# christmas_card.net
KiCad netlist of a schematic drawn in EAGLE
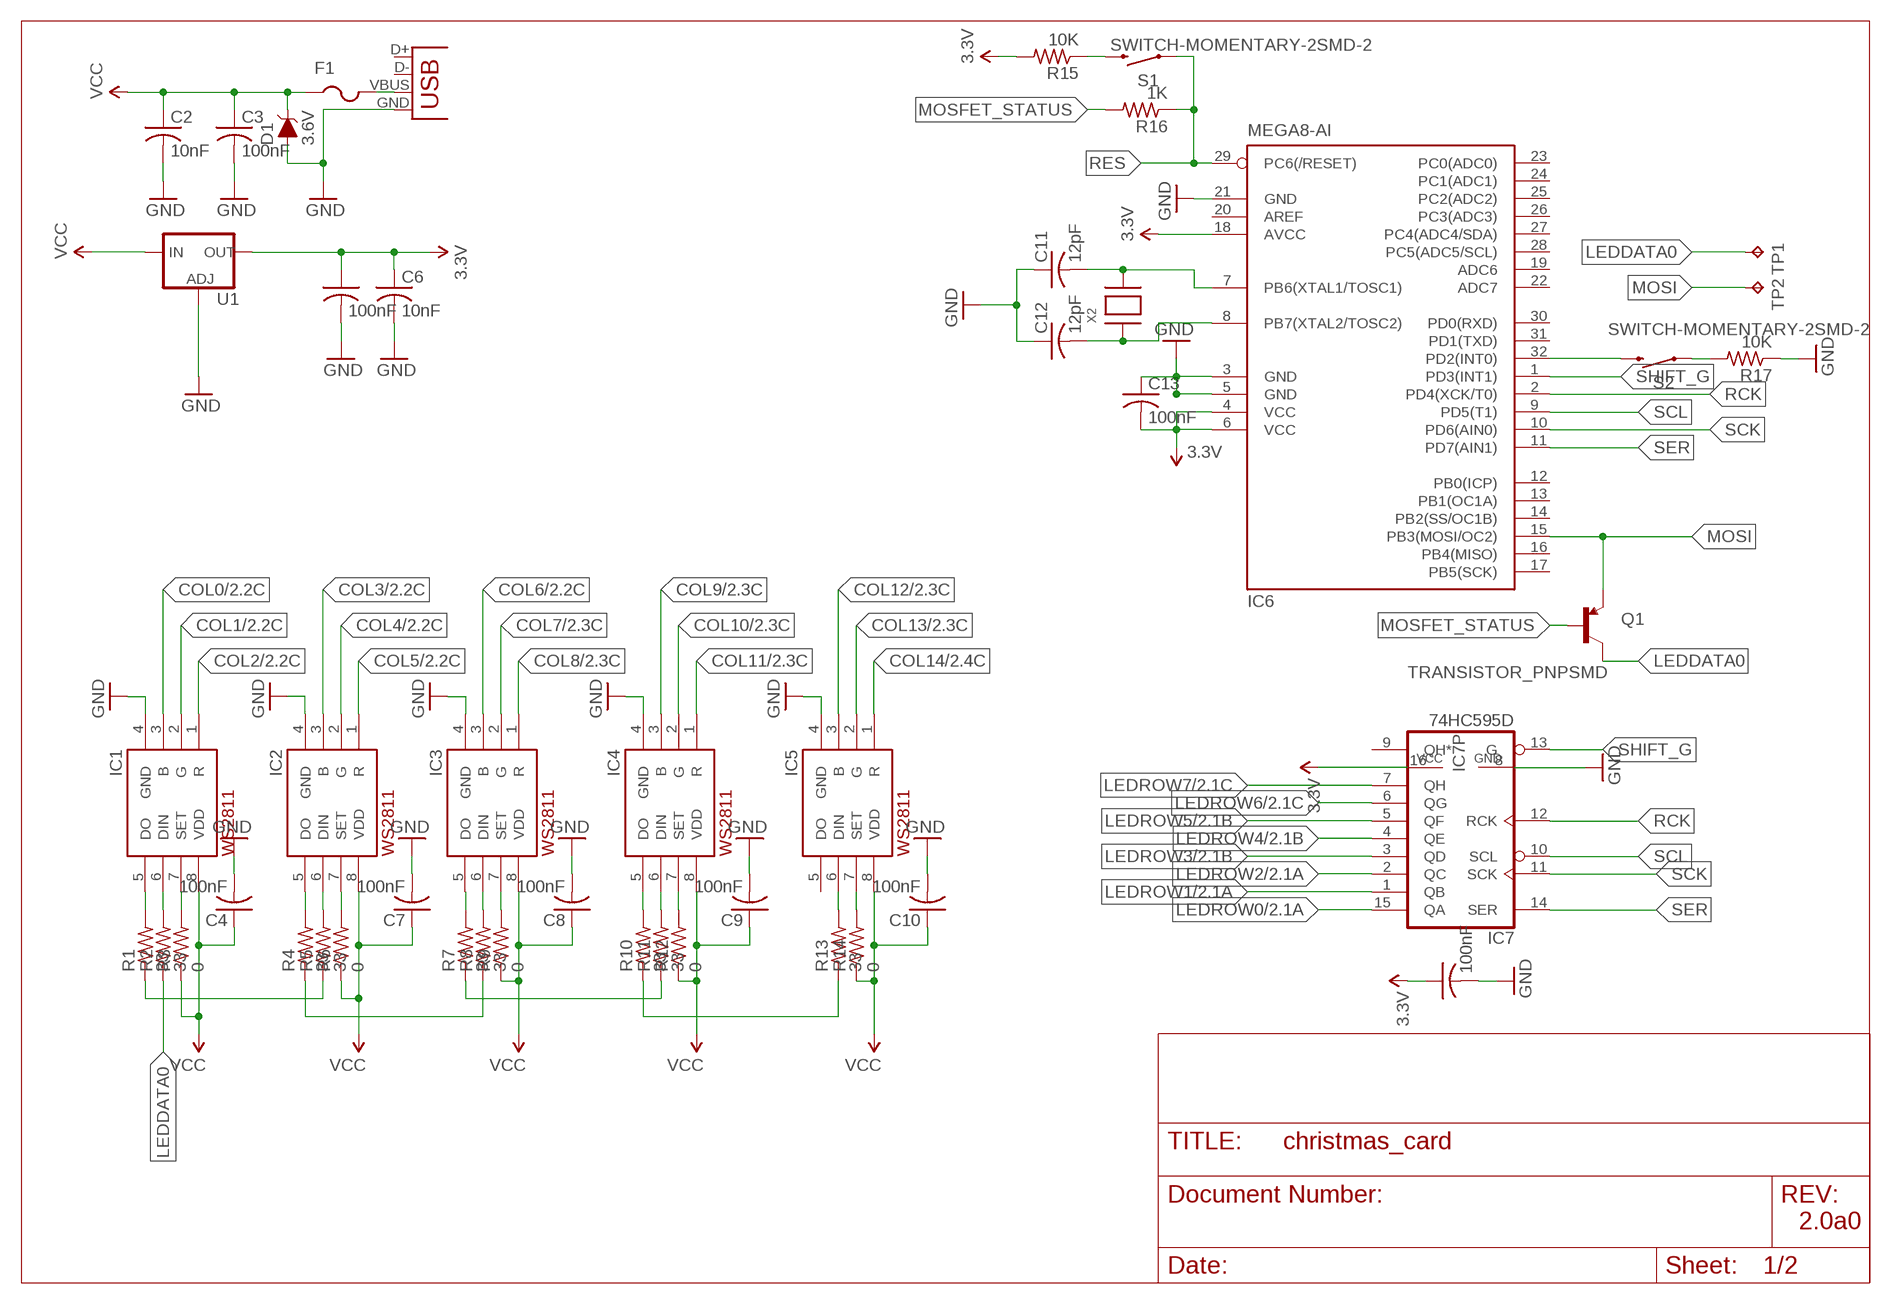
[diagram p0: schematic, sheet 1]
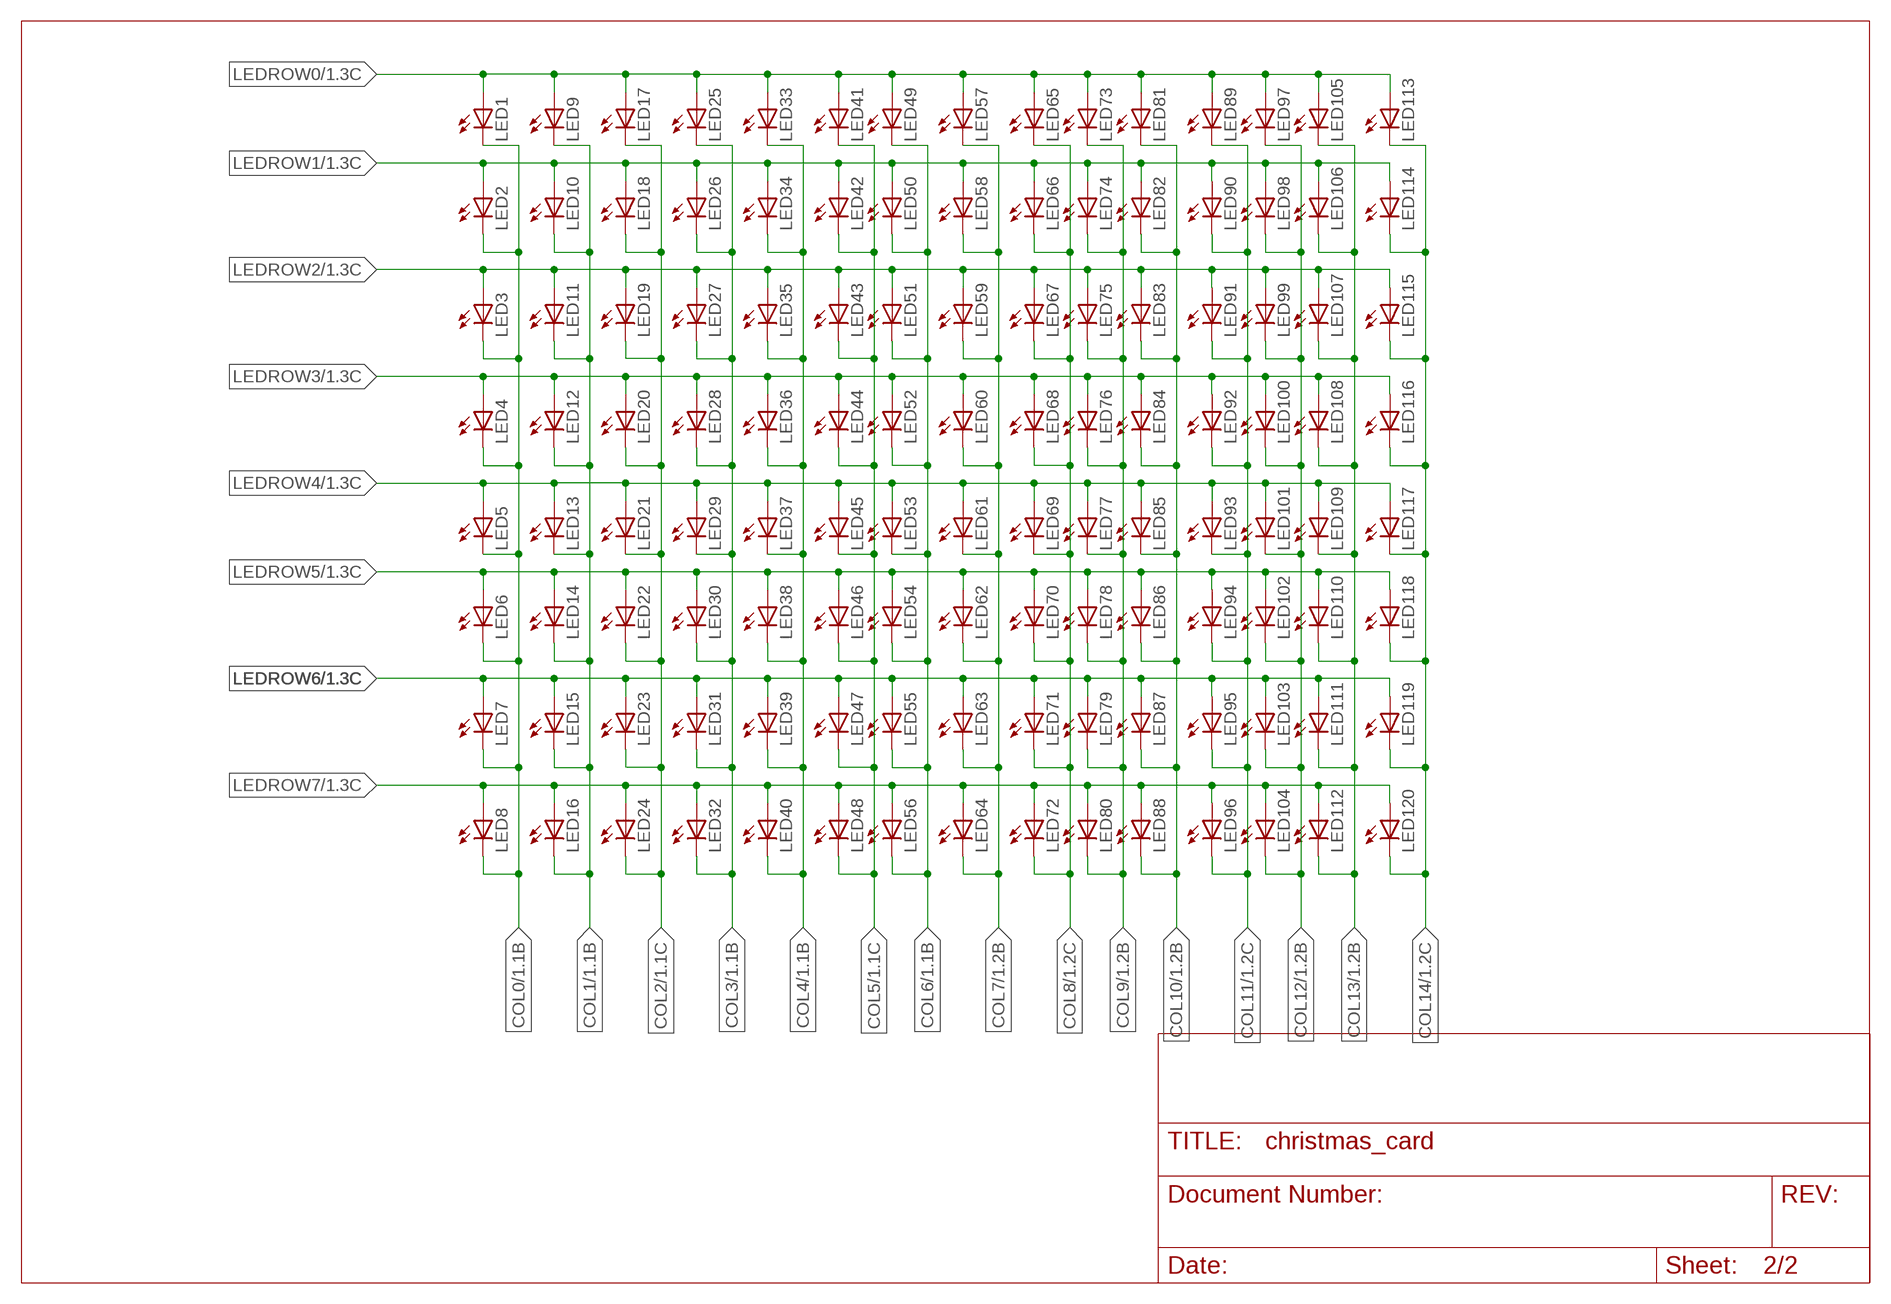
[diagram p1: schematic, sheet 2]

(export (version "E")
  (design (tool "Eeschema 10.0.6"))
  (components
    (comp (ref "LED1")
      (value "LED1206")
      (footprint "eagle-import:LED-1206")
      (libsource (lib "eagle-import") (part "LED1206"))
    )
    (comp (ref "LED2")
      (value "LED1206")
      (footprint "eagle-import:LED-1206")
      (libsource (lib "eagle-import") (part "LED1206"))
    )
    (comp (ref "LED3")
      (value "LED1206")
      (footprint "eagle-import:LED-1206")
      (libsource (lib "eagle-import") (part "LED1206"))
    )
    (comp (ref "LED4")
      (value "LED1206")
      (footprint "eagle-import:LED-1206")
      (libsource (lib "eagle-import") (part "LED1206"))
    )
    (comp (ref "LED5")
      (value "LED1206")
      (footprint "eagle-import:LED-1206")
      (libsource (lib "eagle-import") (part "LED1206"))
    )
    (comp (ref "LED6")
      (value "LED1206")
      (footprint "eagle-import:LED-1206")
      (libsource (lib "eagle-import") (part "LED1206"))
    )
    (comp (ref "LED7")
      (value "LED1206")
      (footprint "eagle-import:LED-1206")
      (libsource (lib "eagle-import") (part "LED1206"))
    )
    (comp (ref "LED8")
      (value "LED1206")
      (footprint "eagle-import:LED-1206")
      (libsource (lib "eagle-import") (part "LED1206"))
    )
    (comp (ref "LED9")
      (value "LED1206")
      (footprint "eagle-import:LED-1206")
      (libsource (lib "eagle-import") (part "LED1206"))
    )
    (comp (ref "LED10")
      (value "LED1206")
      (footprint "eagle-import:LED-1206")
      (libsource (lib "eagle-import") (part "LED1206"))
    )
    (comp (ref "LED11")
      (value "LED1206")
      (footprint "eagle-import:LED-1206")
      (libsource (lib "eagle-import") (part "LED1206"))
    )
    (comp (ref "LED12")
      (value "LED1206")
      (footprint "eagle-import:LED-1206")
      (libsource (lib "eagle-import") (part "LED1206"))
    )
    (comp (ref "LED13")
      (value "LED1206")
      (footprint "eagle-import:LED-1206")
      (libsource (lib "eagle-import") (part "LED1206"))
    )
    (comp (ref "LED14")
      (value "LED1206")
      (footprint "eagle-import:LED-1206")
      (libsource (lib "eagle-import") (part "LED1206"))
    )
    (comp (ref "LED15")
      (value "LED1206")
      (footprint "eagle-import:LED-1206")
      (libsource (lib "eagle-import") (part "LED1206"))
    )
    (comp (ref "LED16")
      (value "LED1206")
      (footprint "eagle-import:LED-1206")
      (libsource (lib "eagle-import") (part "LED1206"))
    )
    (comp (ref "LED17")
      (value "LED1206")
      (footprint "eagle-import:LED-1206")
      (libsource (lib "eagle-import") (part "LED1206"))
    )
    (comp (ref "LED18")
      (value "LED1206")
      (footprint "eagle-import:LED-1206")
      (libsource (lib "eagle-import") (part "LED1206"))
    )
    (comp (ref "LED19")
      (value "LED1206")
      (footprint "eagle-import:LED-1206")
      (libsource (lib "eagle-import") (part "LED1206"))
    )
    (comp (ref "LED20")
      (value "LED1206")
      (footprint "eagle-import:LED-1206")
      (libsource (lib "eagle-import") (part "LED1206"))
    )
    (comp (ref "LED21")
      (value "LED1206")
      (footprint "eagle-import:LED-1206")
      (libsource (lib "eagle-import") (part "LED1206"))
    )
    (comp (ref "LED22")
      (value "LED1206")
      (footprint "eagle-import:LED-1206")
      (libsource (lib "eagle-import") (part "LED1206"))
    )
    (comp (ref "LED23")
      (value "LED1206")
      (footprint "eagle-import:LED-1206")
      (libsource (lib "eagle-import") (part "LED1206"))
    )
    (comp (ref "LED24")
      (value "LED1206")
      (footprint "eagle-import:LED-1206")
      (libsource (lib "eagle-import") (part "LED1206"))
    )
    (comp (ref "LED25")
      (value "LED1206")
      (footprint "eagle-import:LED-1206")
      (libsource (lib "eagle-import") (part "LED1206"))
    )
    (comp (ref "LED26")
      (value "LED1206")
      (footprint "eagle-import:LED-1206")
      (libsource (lib "eagle-import") (part "LED1206"))
    )
    (comp (ref "LED27")
      (value "LED1206")
      (footprint "eagle-import:LED-1206")
      (libsource (lib "eagle-import") (part "LED1206"))
    )
    (comp (ref "LED28")
      (value "LED1206")
      (footprint "eagle-import:LED-1206")
      (libsource (lib "eagle-import") (part "LED1206"))
    )
    (comp (ref "LED29")
      (value "LED1206")
      (footprint "eagle-import:LED-1206")
      (libsource (lib "eagle-import") (part "LED1206"))
    )
    (comp (ref "LED30")
      (value "LED1206")
      (footprint "eagle-import:LED-1206")
      (libsource (lib "eagle-import") (part "LED1206"))
    )
    (comp (ref "LED31")
      (value "LED1206")
      (footprint "eagle-import:LED-1206")
      (libsource (lib "eagle-import") (part "LED1206"))
    )
    (comp (ref "LED32")
      (value "LED1206")
      (footprint "eagle-import:LED-1206")
      (libsource (lib "eagle-import") (part "LED1206"))
    )
    (comp (ref "LED33")
      (value "LED1206")
      (footprint "eagle-import:LED-1206")
      (libsource (lib "eagle-import") (part "LED1206"))
    )
    (comp (ref "LED34")
      (value "LED1206")
      (footprint "eagle-import:LED-1206")
      (libsource (lib "eagle-import") (part "LED1206"))
    )
    (comp (ref "LED35")
      (value "LED1206")
      (footprint "eagle-import:LED-1206")
      (libsource (lib "eagle-import") (part "LED1206"))
    )
    (comp (ref "LED36")
      (value "LED1206")
      (footprint "eagle-import:LED-1206")
      (libsource (lib "eagle-import") (part "LED1206"))
    )
    (comp (ref "LED37")
      (value "LED1206")
      (footprint "eagle-import:LED-1206")
      (libsource (lib "eagle-import") (part "LED1206"))
    )
    (comp (ref "LED38")
      (value "LED1206")
      (footprint "eagle-import:LED-1206")
      (libsource (lib "eagle-import") (part "LED1206"))
    )
    (comp (ref "LED39")
      (value "LED1206")
      (footprint "eagle-import:LED-1206")
      (libsource (lib "eagle-import") (part "LED1206"))
    )
    (comp (ref "LED40")
      (value "LED1206")
      (footprint "eagle-import:LED-1206")
      (libsource (lib "eagle-import") (part "LED1206"))
    )
    (comp (ref "LED41")
      (value "LED1206")
      (footprint "eagle-import:LED-1206")
      (libsource (lib "eagle-import") (part "LED1206"))
    )
    (comp (ref "LED42")
      (value "LED1206")
      (footprint "eagle-import:LED-1206")
      (libsource (lib "eagle-import") (part "LED1206"))
    )
    (comp (ref "LED43")
      (value "LED1206")
      (footprint "eagle-import:LED-1206")
      (libsource (lib "eagle-import") (part "LED1206"))
    )
    (comp (ref "LED44")
      (value "LED1206")
      (footprint "eagle-import:LED-1206")
      (libsource (lib "eagle-import") (part "LED1206"))
    )
    (comp (ref "LED45")
      (value "LED1206")
      (footprint "eagle-import:LED-1206")
      (libsource (lib "eagle-import") (part "LED1206"))
    )
    (comp (ref "LED46")
      (value "LED1206")
      (footprint "eagle-import:LED-1206")
      (libsource (lib "eagle-import") (part "LED1206"))
    )
    (comp (ref "LED47")
      (value "LED1206")
      (footprint "eagle-import:LED-1206")
      (libsource (lib "eagle-import") (part "LED1206"))
    )
    (comp (ref "LED48")
      (value "LED1206")
      (footprint "eagle-import:LED-1206")
      (libsource (lib "eagle-import") (part "LED1206"))
    )
    (comp (ref "LED49")
      (value "LED1206")
      (footprint "eagle-import:LED-1206")
      (libsource (lib "eagle-import") (part "LED1206"))
    )
    (comp (ref "LED50")
      (value "LED1206")
      (footprint "eagle-import:LED-1206")
      (libsource (lib "eagle-import") (part "LED1206"))
    )
    (comp (ref "LED51")
      (value "LED1206")
      (footprint "eagle-import:LED-1206")
      (libsource (lib "eagle-import") (part "LED1206"))
    )
    (comp (ref "LED52")
      (value "LED1206")
      (footprint "eagle-import:LED-1206")
      (libsource (lib "eagle-import") (part "LED1206"))
    )
    (comp (ref "LED53")
      (value "LED1206")
      (footprint "eagle-import:LED-1206")
      (libsource (lib "eagle-import") (part "LED1206"))
    )
    (comp (ref "LED54")
      (value "LED1206")
      (footprint "eagle-import:LED-1206")
      (libsource (lib "eagle-import") (part "LED1206"))
    )
    (comp (ref "LED55")
      (value "LED1206")
      (footprint "eagle-import:LED-1206")
      (libsource (lib "eagle-import") (part "LED1206"))
    )
    (comp (ref "LED56")
      (value "LED1206")
      (footprint "eagle-import:LED-1206")
      (libsource (lib "eagle-import") (part "LED1206"))
    )
    (comp (ref "LED57")
      (value "LED1206")
      (footprint "eagle-import:LED-1206")
      (libsource (lib "eagle-import") (part "LED1206"))
    )
    (comp (ref "LED58")
      (value "LED1206")
      (footprint "eagle-import:LED-1206")
      (libsource (lib "eagle-import") (part "LED1206"))
    )
    (comp (ref "LED59")
      (value "LED1206")
      (footprint "eagle-import:LED-1206")
      (libsource (lib "eagle-import") (part "LED1206"))
    )
    (comp (ref "LED60")
      (value "LED1206")
      (footprint "eagle-import:LED-1206")
      (libsource (lib "eagle-import") (part "LED1206"))
    )
    (comp (ref "LED61")
      (value "LED1206")
      (footprint "eagle-import:LED-1206")
      (libsource (lib "eagle-import") (part "LED1206"))
    )
    (comp (ref "LED62")
      (value "LED1206")
      (footprint "eagle-import:LED-1206")
      (libsource (lib "eagle-import") (part "LED1206"))
    )
    (comp (ref "LED63")
      (value "LED1206")
      (footprint "eagle-import:LED-1206")
      (libsource (lib "eagle-import") (part "LED1206"))
    )
    (comp (ref "LED64")
      (value "LED1206")
      (footprint "eagle-import:LED-1206")
      (libsource (lib "eagle-import") (part "LED1206"))
    )
    (comp (ref "LED65")
      (value "LED1206")
      (footprint "eagle-import:LED-1206")
      (libsource (lib "eagle-import") (part "LED1206"))
    )
    (comp (ref "LED66")
      (value "LED1206")
      (footprint "eagle-import:LED-1206")
      (libsource (lib "eagle-import") (part "LED1206"))
    )
    (comp (ref "LED67")
      (value "LED1206")
      (footprint "eagle-import:LED-1206")
      (libsource (lib "eagle-import") (part "LED1206"))
    )
    (comp (ref "LED68")
      (value "LED1206")
      (footprint "eagle-import:LED-1206")
      (libsource (lib "eagle-import") (part "LED1206"))
    )
    (comp (ref "LED69")
      (value "LED1206")
      (footprint "eagle-import:LED-1206")
      (libsource (lib "eagle-import") (part "LED1206"))
    )
    (comp (ref "LED70")
      (value "LED1206")
      (footprint "eagle-import:LED-1206")
      (libsource (lib "eagle-import") (part "LED1206"))
    )
    (comp (ref "LED71")
      (value "LED1206")
      (footprint "eagle-import:LED-1206")
      (libsource (lib "eagle-import") (part "LED1206"))
    )
    (comp (ref "LED72")
      (value "LED1206")
      (footprint "eagle-import:LED-1206")
      (libsource (lib "eagle-import") (part "LED1206"))
    )
    (comp (ref "LED73")
      (value "LED1206")
      (footprint "eagle-import:LED-1206")
      (libsource (lib "eagle-import") (part "LED1206"))
    )
    (comp (ref "LED74")
      (value "LED1206")
      (footprint "eagle-import:LED-1206")
      (libsource (lib "eagle-import") (part "LED1206"))
    )
    (comp (ref "LED75")
      (value "LED1206")
      (footprint "eagle-import:LED-1206")
      (libsource (lib "eagle-import") (part "LED1206"))
    )
    (comp (ref "LED76")
      (value "LED1206")
      (footprint "eagle-import:LED-1206")
      (libsource (lib "eagle-import") (part "LED1206"))
    )
    (comp (ref "LED77")
      (value "LED1206")
      (footprint "eagle-import:LED-1206")
      (libsource (lib "eagle-import") (part "LED1206"))
    )
    (comp (ref "LED78")
      (value "LED1206")
      (footprint "eagle-import:LED-1206")
      (libsource (lib "eagle-import") (part "LED1206"))
    )
    (comp (ref "LED79")
      (value "LED1206")
      (footprint "eagle-import:LED-1206")
      (libsource (lib "eagle-import") (part "LED1206"))
    )
    (comp (ref "LED80")
      (value "LED1206")
      (footprint "eagle-import:LED-1206")
      (libsource (lib "eagle-import") (part "LED1206"))
    )
    (comp (ref "LED81")
      (value "LED1206")
      (footprint "eagle-import:LED-1206")
      (libsource (lib "eagle-import") (part "LED1206"))
    )
    (comp (ref "LED82")
      (value "LED1206")
      (footprint "eagle-import:LED-1206")
      (libsource (lib "eagle-import") (part "LED1206"))
    )
    (comp (ref "LED83")
      (value "LED1206")
      (footprint "eagle-import:LED-1206")
      (libsource (lib "eagle-import") (part "LED1206"))
    )
    (comp (ref "LED84")
      (value "LED1206")
      (footprint "eagle-import:LED-1206")
      (libsource (lib "eagle-import") (part "LED1206"))
    )
    (comp (ref "LED85")
      (value "LED1206")
      (footprint "eagle-import:LED-1206")
      (libsource (lib "eagle-import") (part "LED1206"))
    )
    (comp (ref "LED86")
      (value "LED1206")
      (footprint "eagle-import:LED-1206")
      (libsource (lib "eagle-import") (part "LED1206"))
    )
    (comp (ref "LED87")
      (value "LED1206")
      (footprint "eagle-import:LED-1206")
      (libsource (lib "eagle-import") (part "LED1206"))
    )
    (comp (ref "LED88")
      (value "LED1206")
      (footprint "eagle-import:LED-1206")
      (libsource (lib "eagle-import") (part "LED1206"))
    )
    (comp (ref "LED89")
      (value "LED1206")
      (footprint "eagle-import:LED-1206")
      (libsource (lib "eagle-import") (part "LED1206"))
    )
    (comp (ref "LED90")
      (value "LED1206")
      (footprint "eagle-import:LED-1206")
      (libsource (lib "eagle-import") (part "LED1206"))
    )
    (comp (ref "LED91")
      (value "LED1206")
      (footprint "eagle-import:LED-1206")
      (libsource (lib "eagle-import") (part "LED1206"))
    )
    (comp (ref "LED92")
      (value "LED1206")
      (footprint "eagle-import:LED-1206")
      (libsource (lib "eagle-import") (part "LED1206"))
    )
    (comp (ref "LED93")
      (value "LED1206")
      (footprint "eagle-import:LED-1206")
      (libsource (lib "eagle-import") (part "LED1206"))
    )
    (comp (ref "LED94")
      (value "LED1206")
      (footprint "eagle-import:LED-1206")
      (libsource (lib "eagle-import") (part "LED1206"))
    )
    (comp (ref "LED95")
      (value "LED1206")
      (footprint "eagle-import:LED-1206")
      (libsource (lib "eagle-import") (part "LED1206"))
    )
    (comp (ref "LED96")
      (value "LED1206")
      (footprint "eagle-import:LED-1206")
      (libsource (lib "eagle-import") (part "LED1206"))
    )
    (comp (ref "LED97")
      (value "LED1206")
      (footprint "eagle-import:LED-1206")
      (libsource (lib "eagle-import") (part "LED1206"))
    )
    (comp (ref "LED98")
      (value "LED1206")
      (footprint "eagle-import:LED-1206")
      (libsource (lib "eagle-import") (part "LED1206"))
    )
    (comp (ref "LED99")
      (value "LED1206")
      (footprint "eagle-import:LED-1206")
      (libsource (lib "eagle-import") (part "LED1206"))
    )
    (comp (ref "LED100")
      (value "LED1206")
      (footprint "eagle-import:LED-1206")
      (libsource (lib "eagle-import") (part "LED1206"))
    )
    (comp (ref "LED101")
      (value "LED1206")
      (footprint "eagle-import:LED-1206")
      (libsource (lib "eagle-import") (part "LED1206"))
    )
    (comp (ref "LED102")
      (value "LED1206")
      (footprint "eagle-import:LED-1206")
      (libsource (lib "eagle-import") (part "LED1206"))
    )
    (comp (ref "LED103")
      (value "LED1206")
      (footprint "eagle-import:LED-1206")
      (libsource (lib "eagle-import") (part "LED1206"))
    )
    (comp (ref "LED104")
      (value "LED1206")
      (footprint "eagle-import:LED-1206")
      (libsource (lib "eagle-import") (part "LED1206"))
    )
    (comp (ref "LED105")
      (value "LED1206")
      (footprint "eagle-import:LED-1206")
      (libsource (lib "eagle-import") (part "LED1206"))
    )
    (comp (ref "LED106")
      (value "LED1206")
      (footprint "eagle-import:LED-1206")
      (libsource (lib "eagle-import") (part "LED1206"))
    )
    (comp (ref "LED107")
      (value "LED1206")
      (footprint "eagle-import:LED-1206")
      (libsource (lib "eagle-import") (part "LED1206"))
    )
    (comp (ref "LED108")
      (value "LED1206")
      (footprint "eagle-import:LED-1206")
      (libsource (lib "eagle-import") (part "LED1206"))
    )
    (comp (ref "LED109")
      (value "LED1206")
      (footprint "eagle-import:LED-1206")
      (libsource (lib "eagle-import") (part "LED1206"))
    )
    (comp (ref "LED110")
      (value "LED1206")
      (footprint "eagle-import:LED-1206")
      (libsource (lib "eagle-import") (part "LED1206"))
    )
    (comp (ref "LED111")
      (value "LED1206")
      (footprint "eagle-import:LED-1206")
      (libsource (lib "eagle-import") (part "LED1206"))
    )
    (comp (ref "LED112")
      (value "LED1206")
      (footprint "eagle-import:LED-1206")
      (libsource (lib "eagle-import") (part "LED1206"))
    )
    (comp (ref "LED113")
      (value "LED1206")
      (footprint "eagle-import:LED-1206")
      (libsource (lib "eagle-import") (part "LED1206"))
    )
    (comp (ref "LED114")
      (value "LED1206")
      (footprint "eagle-import:LED-1206")
      (libsource (lib "eagle-import") (part "LED1206"))
    )
    (comp (ref "LED115")
      (value "LED1206")
      (footprint "eagle-import:LED-1206")
      (libsource (lib "eagle-import") (part "LED1206"))
    )
    (comp (ref "LED116")
      (value "LED1206")
      (footprint "eagle-import:LED-1206")
      (libsource (lib "eagle-import") (part "LED1206"))
    )
    (comp (ref "LED117")
      (value "LED1206")
      (footprint "eagle-import:LED-1206")
      (libsource (lib "eagle-import") (part "LED1206"))
    )
    (comp (ref "LED118")
      (value "LED1206")
      (footprint "eagle-import:LED-1206")
      (libsource (lib "eagle-import") (part "LED1206"))
    )
    (comp (ref "LED119")
      (value "LED1206")
      (footprint "eagle-import:LED-1206")
      (libsource (lib "eagle-import") (part "LED1206"))
    )
    (comp (ref "LED120")
      (value "LED1206")
      (footprint "eagle-import:LED-1206")
      (libsource (lib "eagle-import") (part "LED1206"))
    )
    (comp (ref "C2")
      (value "10nF")
      (footprint "eagle-import:C0603")
      (libsource (lib "eagle-import") (part "C-USC0603"))
    )
    (comp (ref "C3")
      (value "100nF")
      (footprint "eagle-import:C0603")
      (libsource (lib "eagle-import") (part "C-USC0603"))
    )
    (comp (ref "C4")
      (value "100nF")
      (footprint "eagle-import:C0603")
      (libsource (lib "eagle-import") (part "C-USC0603"))
    )
    (comp (ref "C5")
      (value "100nF")
      (footprint "eagle-import:C0603")
      (libsource (lib "eagle-import") (part "C-USC0603"))
    )
    (comp (ref "C6")
      (value "10nF")
      (footprint "eagle-import:C0603")
      (libsource (lib "eagle-import") (part "C-USC0603"))
    )
    (comp (ref "C7")
      (value "100nF")
      (footprint "eagle-import:C0603")
      (libsource (lib "eagle-import") (part "C-USC0603"))
    )
    (comp (ref "C8")
      (value "100nF")
      (footprint "eagle-import:C0603")
      (libsource (lib "eagle-import") (part "C-USC0603"))
    )
    (comp (ref "C9")
      (value "100nF")
      (footprint "eagle-import:C0603")
      (libsource (lib "eagle-import") (part "C-USC0603"))
    )
    (comp (ref "C10")
      (value "100nF")
      (footprint "eagle-import:C0603")
      (libsource (lib "eagle-import") (part "C-USC0603"))
    )
    (comp (ref "C11")
      (value "12pF")
      (footprint "eagle-import:C0603")
      (libsource (lib "eagle-import") (part "C-USC0603"))
    )
    (comp (ref "C12")
      (value "12pF")
      (footprint "eagle-import:C0603")
      (libsource (lib "eagle-import") (part "C-USC0603"))
    )
    (comp (ref "C13")
      (value "100nF")
      (footprint "eagle-import:C0603")
      (libsource (lib "eagle-import") (part "C-USC0603"))
    )
    (comp (ref "C14")
      (value "100nF")
      (footprint "eagle-import:C0603")
      (libsource (lib "eagle-import") (part "C-USC0603"))
    )
    (comp (ref "D1")
      (value "3.6V")
      (footprint "eagle-import:SOD-323")
      (libsource (lib "eagle-import") (part "DIODE-ZENER-BZT52C3V6S"))
    )
    (comp (ref "F1")
      (value "PTCFUSE-1206")
      (footprint "eagle-import:R1206")
      (libsource (lib "eagle-import") (part "PTCFUSE-1206"))
    )
    (comp (ref "IC1")
      (value "WS2811-SOP8")
      (footprint "eagle-import:SO08-SKINNYPADS")
      (libsource (lib "eagle-import") (part "WS2811-SOP8"))
    )
    (comp (ref "IC2")
      (value "WS2811-SOP8")
      (footprint "eagle-import:SO08-SKINNYPADS")
      (libsource (lib "eagle-import") (part "WS2811-SOP8"))
    )
    (comp (ref "IC3")
      (value "WS2811-SOP8")
      (footprint "eagle-import:SO08-SKINNYPADS")
      (libsource (lib "eagle-import") (part "WS2811-SOP8"))
    )
    (comp (ref "IC4")
      (value "WS2811-SOP8")
      (footprint "eagle-import:SO08-SKINNYPADS")
      (libsource (lib "eagle-import") (part "WS2811-SOP8"))
    )
    (comp (ref "IC5")
      (value "WS2811-SOP8")
      (footprint "eagle-import:SO08-SKINNYPADS")
      (libsource (lib "eagle-import") (part "WS2811-SOP8"))
    )
    (comp (ref "IC6")
      (value "MEGA8-AI")
      (footprint "eagle-import:TQFP32-08")
      (fields (field (name "MPN") "ATMEGA8-16AU"))
      (libsource (lib "eagle-import") (part "MEGA8-AI"))
    )
    (comp (ref "IC7")
      (value "74HC595D")
      (footprint "eagle-import:SO16")
      (libsource (lib "eagle-import") (part "74595DHC"))
    )
    (comp (ref "Q1")
      (value "TRANSISTOR_PNPSMD")
      (footprint "eagle-import:SOT23-3")
      (libsource (lib "eagle-import") (part "TRANSISTOR_PNPSMD"))
    )
    (comp (ref "R1")
      (value "33")
      (footprint "eagle-import:R0603")
      (libsource (lib "eagle-import") (part "R-US_R0603"))
    )
    (comp (ref "R2")
      (value "33")
      (footprint "eagle-import:R0603")
      (libsource (lib "eagle-import") (part "R-US_R0603"))
    )
    (comp (ref "R3")
      (value "0")
      (footprint "eagle-import:R0603")
      (libsource (lib "eagle-import") (part "R-US_R0603"))
    )
    (comp (ref "R4")
      (value "33")
      (footprint "eagle-import:R0603")
      (libsource (lib "eagle-import") (part "R-US_R0603"))
    )
    (comp (ref "R5")
      (value "33")
      (footprint "eagle-import:R0603")
      (libsource (lib "eagle-import") (part "R-US_R0603"))
    )
    (comp (ref "R6")
      (value "0")
      (footprint "eagle-import:R0603")
      (libsource (lib "eagle-import") (part "R-US_R0603"))
    )
    (comp (ref "R7")
      (value "33")
      (footprint "eagle-import:R0603")
      (libsource (lib "eagle-import") (part "R-US_R0603"))
    )
    (comp (ref "R8")
      (value "33")
      (footprint "eagle-import:R0603")
      (libsource (lib "eagle-import") (part "R-US_R0603"))
    )
    (comp (ref "R9")
      (value "0")
      (footprint "eagle-import:R0603")
      (libsource (lib "eagle-import") (part "R-US_R0603"))
    )
    (comp (ref "R10")
      (value "33")
      (footprint "eagle-import:R0603")
      (libsource (lib "eagle-import") (part "R-US_R0603"))
    )
    (comp (ref "R11")
      (value "33")
      (footprint "eagle-import:R0603")
      (libsource (lib "eagle-import") (part "R-US_R0603"))
    )
    (comp (ref "R12")
      (value "0")
      (footprint "eagle-import:R0603")
      (libsource (lib "eagle-import") (part "R-US_R0603"))
    )
    (comp (ref "R13")
      (value "33")
      (footprint "eagle-import:R0603")
      (libsource (lib "eagle-import") (part "R-US_R0603"))
    )
    (comp (ref "R14")
      (value "0")
      (footprint "eagle-import:R0603")
      (libsource (lib "eagle-import") (part "R-US_R0603"))
    )
    (comp (ref "R15")
      (value "10K")
      (footprint "eagle-import:R0603")
      (libsource (lib "eagle-import") (part "R-US_R0603"))
    )
    (comp (ref "R16")
      (value "1K")
      (footprint "eagle-import:R0603")
      (libsource (lib "eagle-import") (part "R-US_R0603"))
    )
    (comp (ref "R17")
      (value "10K")
      (footprint "eagle-import:R0603")
      (libsource (lib "eagle-import") (part "R-US_R0603"))
    )
    (comp (ref "S1")
      (value "SWITCH-MOMENTARY-2SMD-2")
      (footprint "eagle-import:TACTILE_SWITCH_SMD-2")
      (libsource (lib "eagle-import") (part "SWITCH-MOMENTARY-2SMD-2"))
    )
    (comp (ref "S2")
      (value "SWITCH-MOMENTARY-2SMD-2")
      (footprint "eagle-import:TACTILE_SWITCH_SMD-2")
      (libsource (lib "eagle-import") (part "SWITCH-MOMENTARY-2SMD-2"))
    )
    (comp (ref "TP1")
      (value "TPB1,27")
      (footprint "eagle-import:B1,27")
      (libsource (lib "eagle-import") (part "TPB1,27"))
    )
    (comp (ref "TP2")
      (value "TPB1,27")
      (footprint "eagle-import:B1,27")
      (libsource (lib "eagle-import") (part "TPB1,27"))
    )
    (comp (ref "U1")
      (value "V_REG_LM1117SOT223")
      (footprint "eagle-import:SOT223")
      (libsource (lib "eagle-import") (part "V_REG_LM1117SOT223"))
    )
    (comp (ref "X1")
      (value "USB-MICROB")
      (footprint "eagle-import:USB-MICROB")
      (libsource (lib "eagle-import") (part "USB-MICROB"))
    )
    (comp (ref "X2")
      (value "XTALNX5032")
      (footprint "eagle-import:NX5032")
      (libsource (lib "eagle-import") (part "XTALNX5032"))
    )
  )
  (nets
    (net (code "1") (name "3.3V") (class "Default")
      (node (ref "C13") (pin "2") (pinfunction "2_2") (pintype "passive"))
      (node (ref "C14") (pin "1") (pinfunction "1_1") (pintype "passive"))
      (node (ref "C5") (pin "1") (pinfunction "1_1") (pintype "passive"))
      (node (ref "C6") (pin "1") (pinfunction "1_1") (pintype "passive"))
      (node (ref "IC6") (pin "18") (pinfunction "AVCC_18") (pintype "power_in"))
      (node (ref "IC6") (pin "4") (pinfunction "VCC_4") (pintype "power_in"))
      (node (ref "IC6") (pin "6") (pinfunction "VCC_6") (pintype "power_in"))
      (node (ref "IC7") (pin "16") (pinfunction "VCC_16") (pintype "power_in"))
      (node (ref "R15") (pin "2") (pinfunction "2_2") (pintype "passive"))
      (node (ref "U1") (pin "2") (pinfunction "OUT_2") (pintype "output"))
      (node (ref "U1") (pin "4") (pinfunction "OUT_4") (pintype "output"))
    )
    (net (code "2") (name "COL0") (class "Default")
      (node (ref "IC1") (pin "3") (pinfunction "B_3") (pintype "open_collector"))
      (node (ref "LED1") (pin "C") (pinfunction "C_C") (pintype "passive"))
      (node (ref "LED2") (pin "C") (pinfunction "C_C") (pintype "passive"))
      (node (ref "LED3") (pin "C") (pinfunction "C_C") (pintype "passive"))
      (node (ref "LED4") (pin "C") (pinfunction "C_C") (pintype "passive"))
      (node (ref "LED5") (pin "C") (pinfunction "C_C") (pintype "passive"))
      (node (ref "LED6") (pin "C") (pinfunction "C_C") (pintype "passive"))
      (node (ref "LED7") (pin "C") (pinfunction "C_C") (pintype "passive"))
      (node (ref "LED8") (pin "C") (pinfunction "C_C") (pintype "passive"))
    )
    (net (code "3") (name "COL1") (class "Default")
      (node (ref "IC1") (pin "2") (pinfunction "G_2") (pintype "open_collector"))
      (node (ref "LED10") (pin "C") (pinfunction "C_C") (pintype "passive"))
      (node (ref "LED11") (pin "C") (pinfunction "C_C") (pintype "passive"))
      (node (ref "LED12") (pin "C") (pinfunction "C_C") (pintype "passive"))
      (node (ref "LED13") (pin "C") (pinfunction "C_C") (pintype "passive"))
      (node (ref "LED14") (pin "C") (pinfunction "C_C") (pintype "passive"))
      (node (ref "LED15") (pin "C") (pinfunction "C_C") (pintype "passive"))
      (node (ref "LED16") (pin "C") (pinfunction "C_C") (pintype "passive"))
      (node (ref "LED9") (pin "C") (pinfunction "C_C") (pintype "passive"))
    )
    (net (code "4") (name "COL2") (class "Default")
      (node (ref "IC1") (pin "1") (pinfunction "R_1") (pintype "open_collector"))
      (node (ref "LED17") (pin "C") (pinfunction "C_C") (pintype "passive"))
      (node (ref "LED18") (pin "C") (pinfunction "C_C") (pintype "passive"))
      (node (ref "LED19") (pin "C") (pinfunction "C_C") (pintype "passive"))
      (node (ref "LED20") (pin "C") (pinfunction "C_C") (pintype "passive"))
      (node (ref "LED21") (pin "C") (pinfunction "C_C") (pintype "passive"))
      (node (ref "LED22") (pin "C") (pinfunction "C_C") (pintype "passive"))
      (node (ref "LED23") (pin "C") (pinfunction "C_C") (pintype "passive"))
      (node (ref "LED24") (pin "C") (pinfunction "C_C") (pintype "passive"))
    )
    (net (code "5") (name "COL3") (class "Default")
      (node (ref "IC2") (pin "3") (pinfunction "B_3") (pintype "open_collector"))
      (node (ref "LED25") (pin "C") (pinfunction "C_C") (pintype "passive"))
      (node (ref "LED26") (pin "C") (pinfunction "C_C") (pintype "passive"))
      (node (ref "LED27") (pin "C") (pinfunction "C_C") (pintype "passive"))
      (node (ref "LED28") (pin "C") (pinfunction "C_C") (pintype "passive"))
      (node (ref "LED29") (pin "C") (pinfunction "C_C") (pintype "passive"))
      (node (ref "LED30") (pin "C") (pinfunction "C_C") (pintype "passive"))
      (node (ref "LED31") (pin "C") (pinfunction "C_C") (pintype "passive"))
      (node (ref "LED32") (pin "C") (pinfunction "C_C") (pintype "passive"))
    )
    (net (code "6") (name "COL4") (class "Default")
      (node (ref "IC2") (pin "2") (pinfunction "G_2") (pintype "open_collector"))
      (node (ref "LED33") (pin "C") (pinfunction "C_C") (pintype "passive"))
      (node (ref "LED34") (pin "C") (pinfunction "C_C") (pintype "passive"))
      (node (ref "LED35") (pin "C") (pinfunction "C_C") (pintype "passive"))
      (node (ref "LED36") (pin "C") (pinfunction "C_C") (pintype "passive"))
      (node (ref "LED37") (pin "C") (pinfunction "C_C") (pintype "passive"))
      (node (ref "LED38") (pin "C") (pinfunction "C_C") (pintype "passive"))
      (node (ref "LED39") (pin "C") (pinfunction "C_C") (pintype "passive"))
      (node (ref "LED40") (pin "C") (pinfunction "C_C") (pintype "passive"))
    )
    (net (code "7") (name "COL5") (class "Default")
      (node (ref "IC2") (pin "1") (pinfunction "R_1") (pintype "open_collector"))
      (node (ref "LED41") (pin "C") (pinfunction "C_C") (pintype "passive"))
      (node (ref "LED42") (pin "C") (pinfunction "C_C") (pintype "passive"))
      (node (ref "LED43") (pin "C") (pinfunction "C_C") (pintype "passive"))
      (node (ref "LED44") (pin "C") (pinfunction "C_C") (pintype "passive"))
      (node (ref "LED45") (pin "C") (pinfunction "C_C") (pintype "passive"))
      (node (ref "LED46") (pin "C") (pinfunction "C_C") (pintype "passive"))
      (node (ref "LED47") (pin "C") (pinfunction "C_C") (pintype "passive"))
      (node (ref "LED48") (pin "C") (pinfunction "C_C") (pintype "passive"))
    )
    (net (code "8") (name "COL6") (class "Default")
      (node (ref "IC3") (pin "3") (pinfunction "B_3") (pintype "open_collector"))
      (node (ref "LED49") (pin "C") (pinfunction "C_C") (pintype "passive"))
      (node (ref "LED50") (pin "C") (pinfunction "C_C") (pintype "passive"))
      (node (ref "LED51") (pin "C") (pinfunction "C_C") (pintype "passive"))
      (node (ref "LED52") (pin "C") (pinfunction "C_C") (pintype "passive"))
      (node (ref "LED53") (pin "C") (pinfunction "C_C") (pintype "passive"))
      (node (ref "LED54") (pin "C") (pinfunction "C_C") (pintype "passive"))
      (node (ref "LED55") (pin "C") (pinfunction "C_C") (pintype "passive"))
      (node (ref "LED56") (pin "C") (pinfunction "C_C") (pintype "passive"))
    )
    (net (code "9") (name "COL7") (class "Default")
      (node (ref "IC3") (pin "2") (pinfunction "G_2") (pintype "open_collector"))
      (node (ref "LED57") (pin "C") (pinfunction "C_C") (pintype "passive"))
      (node (ref "LED58") (pin "C") (pinfunction "C_C") (pintype "passive"))
      (node (ref "LED59") (pin "C") (pinfunction "C_C") (pintype "passive"))
      (node (ref "LED60") (pin "C") (pinfunction "C_C") (pintype "passive"))
      (node (ref "LED61") (pin "C") (pinfunction "C_C") (pintype "passive"))
      (node (ref "LED62") (pin "C") (pinfunction "C_C") (pintype "passive"))
      (node (ref "LED63") (pin "C") (pinfunction "C_C") (pintype "passive"))
      (node (ref "LED64") (pin "C") (pinfunction "C_C") (pintype "passive"))
    )
    (net (code "10") (name "COL8") (class "Default")
      (node (ref "IC3") (pin "1") (pinfunction "R_1") (pintype "open_collector"))
      (node (ref "LED65") (pin "C") (pinfunction "C_C") (pintype "passive"))
      (node (ref "LED66") (pin "C") (pinfunction "C_C") (pintype "passive"))
      (node (ref "LED67") (pin "C") (pinfunction "C_C") (pintype "passive"))
      (node (ref "LED68") (pin "C") (pinfunction "C_C") (pintype "passive"))
      (node (ref "LED69") (pin "C") (pinfunction "C_C") (pintype "passive"))
      (node (ref "LED70") (pin "C") (pinfunction "C_C") (pintype "passive"))
      (node (ref "LED71") (pin "C") (pinfunction "C_C") (pintype "passive"))
      (node (ref "LED72") (pin "C") (pinfunction "C_C") (pintype "passive"))
    )
    (net (code "11") (name "COL9") (class "Default")
      (node (ref "IC4") (pin "3") (pinfunction "B_3") (pintype "open_collector"))
      (node (ref "LED73") (pin "C") (pinfunction "C_C") (pintype "passive"))
      (node (ref "LED74") (pin "C") (pinfunction "C_C") (pintype "passive"))
      (node (ref "LED75") (pin "C") (pinfunction "C_C") (pintype "passive"))
      (node (ref "LED76") (pin "C") (pinfunction "C_C") (pintype "passive"))
      (node (ref "LED77") (pin "C") (pinfunction "C_C") (pintype "passive"))
      (node (ref "LED78") (pin "C") (pinfunction "C_C") (pintype "passive"))
      (node (ref "LED79") (pin "C") (pinfunction "C_C") (pintype "passive"))
      (node (ref "LED80") (pin "C") (pinfunction "C_C") (pintype "passive"))
    )
    (net (code "12") (name "COL10") (class "Default")
      (node (ref "IC4") (pin "2") (pinfunction "G_2") (pintype "open_collector"))
      (node (ref "LED81") (pin "C") (pinfunction "C_C") (pintype "passive"))
      (node (ref "LED82") (pin "C") (pinfunction "C_C") (pintype "passive"))
      (node (ref "LED83") (pin "C") (pinfunction "C_C") (pintype "passive"))
      (node (ref "LED84") (pin "C") (pinfunction "C_C") (pintype "passive"))
      (node (ref "LED85") (pin "C") (pinfunction "C_C") (pintype "passive"))
      (node (ref "LED86") (pin "C") (pinfunction "C_C") (pintype "passive"))
      (node (ref "LED87") (pin "C") (pinfunction "C_C") (pintype "passive"))
      (node (ref "LED88") (pin "C") (pinfunction "C_C") (pintype "passive"))
    )
    (net (code "13") (name "COL11") (class "Default")
      (node (ref "IC4") (pin "1") (pinfunction "R_1") (pintype "open_collector"))
      (node (ref "LED89") (pin "C") (pinfunction "C_C") (pintype "passive"))
      (node (ref "LED90") (pin "C") (pinfunction "C_C") (pintype "passive"))
      (node (ref "LED91") (pin "C") (pinfunction "C_C") (pintype "passive"))
      (node (ref "LED92") (pin "C") (pinfunction "C_C") (pintype "passive"))
      (node (ref "LED93") (pin "C") (pinfunction "C_C") (pintype "passive"))
      (node (ref "LED94") (pin "C") (pinfunction "C_C") (pintype "passive"))
      (node (ref "LED95") (pin "C") (pinfunction "C_C") (pintype "passive"))
      (node (ref "LED96") (pin "C") (pinfunction "C_C") (pintype "passive"))
    )
    (net (code "14") (name "COL12") (class "Default")
      (node (ref "IC5") (pin "3") (pinfunction "B_3") (pintype "open_collector"))
      (node (ref "LED100") (pin "C") (pinfunction "C_C") (pintype "passive"))
      (node (ref "LED101") (pin "C") (pinfunction "C_C") (pintype "passive"))
      (node (ref "LED102") (pin "C") (pinfunction "C_C") (pintype "passive"))
      (node (ref "LED103") (pin "C") (pinfunction "C_C") (pintype "passive"))
      (node (ref "LED104") (pin "C") (pinfunction "C_C") (pintype "passive"))
      (node (ref "LED97") (pin "C") (pinfunction "C_C") (pintype "passive"))
      (node (ref "LED98") (pin "C") (pinfunction "C_C") (pintype "passive"))
      (node (ref "LED99") (pin "C") (pinfunction "C_C") (pintype "passive"))
    )
    (net (code "15") (name "COL13") (class "Default")
      (node (ref "IC5") (pin "2") (pinfunction "G_2") (pintype "open_collector"))
      (node (ref "LED105") (pin "C") (pinfunction "C_C") (pintype "passive"))
      (node (ref "LED106") (pin "C") (pinfunction "C_C") (pintype "passive"))
      (node (ref "LED107") (pin "C") (pinfunction "C_C") (pintype "passive"))
      (node (ref "LED108") (pin "C") (pinfunction "C_C") (pintype "passive"))
      (node (ref "LED109") (pin "C") (pinfunction "C_C") (pintype "passive"))
      (node (ref "LED110") (pin "C") (pinfunction "C_C") (pintype "passive"))
      (node (ref "LED111") (pin "C") (pinfunction "C_C") (pintype "passive"))
      (node (ref "LED112") (pin "C") (pinfunction "C_C") (pintype "passive"))
    )
    (net (code "16") (name "COL14") (class "Default")
      (node (ref "IC5") (pin "1") (pinfunction "R_1") (pintype "open_collector"))
      (node (ref "LED113") (pin "C") (pinfunction "C_C") (pintype "passive"))
      (node (ref "LED114") (pin "C") (pinfunction "C_C") (pintype "passive"))
      (node (ref "LED115") (pin "C") (pinfunction "C_C") (pintype "passive"))
      (node (ref "LED116") (pin "C") (pinfunction "C_C") (pintype "passive"))
      (node (ref "LED117") (pin "C") (pinfunction "C_C") (pintype "passive"))
      (node (ref "LED118") (pin "C") (pinfunction "C_C") (pintype "passive"))
      (node (ref "LED119") (pin "C") (pinfunction "C_C") (pintype "passive"))
      (node (ref "LED120") (pin "C") (pinfunction "C_C") (pintype "passive"))
    )
    (net (code "17") (name "GND") (class "Default")
      (node (ref "C10") (pin "2") (pinfunction "2_2") (pintype "passive"))
      (node (ref "C11") (pin "1") (pinfunction "1_1") (pintype "passive"))
      (node (ref "C12") (pin "1") (pinfunction "1_1") (pintype "passive"))
      (node (ref "C13") (pin "1") (pinfunction "1_1") (pintype "passive"))
      (node (ref "C14") (pin "2") (pinfunction "2_2") (pintype "passive"))
      (node (ref "C2") (pin "2") (pinfunction "2_2") (pintype "passive"))
      (node (ref "C3") (pin "2") (pinfunction "2_2") (pintype "passive"))
      (node (ref "C4") (pin "2") (pinfunction "2_2") (pintype "passive"))
      (node (ref "C5") (pin "2") (pinfunction "2_2") (pintype "passive"))
      (node (ref "C6") (pin "2") (pinfunction "2_2") (pintype "passive"))
      (node (ref "C7") (pin "2") (pinfunction "2_2") (pintype "passive"))
      (node (ref "C8") (pin "2") (pinfunction "2_2") (pintype "passive"))
      (node (ref "C9") (pin "2") (pinfunction "2_2") (pintype "passive"))
      (node (ref "D1") (pin "A") (pinfunction "A_A") (pintype "passive"))
      (node (ref "IC1") (pin "4") (pinfunction "GND_4") (pintype "power_in"))
      (node (ref "IC2") (pin "4") (pinfunction "GND_4") (pintype "power_in"))
      (node (ref "IC3") (pin "4") (pinfunction "GND_4") (pintype "power_in"))
      (node (ref "IC4") (pin "4") (pinfunction "GND_4") (pintype "power_in"))
      (node (ref "IC5") (pin "4") (pinfunction "GND_4") (pintype "power_in"))
      (node (ref "IC6") (pin "21") (pinfunction "GND_21") (pintype "power_in"))
      (node (ref "IC6") (pin "3") (pinfunction "GND_3") (pintype "power_in"))
      (node (ref "IC6") (pin "5") (pinfunction "GND_5") (pintype "power_in"))
      (node (ref "IC7") (pin "8") (pinfunction "GND_8") (pintype "power_in"))
      (node (ref "R17") (pin "1") (pinfunction "1_1") (pintype "passive"))
      (node (ref "U1") (pin "1") (pinfunction "ADJ_1") (pintype "input"))
      (node (ref "X1") (pin "GND") (pinfunction "GND_GND") (pintype "bidirectional"))
    )
    (net (code "18") (name "LEDDATA0") (class "Default")
      (node (ref "Q1") (pin "3") (pinfunction "C_3") (pintype "passive"))
      (node (ref "R2") (pin "1") (pinfunction "1_1") (pintype "passive"))
      (node (ref "TP1") (pin "TP") (pinfunction "TP_TP") (pintype "input"))
    )
    (net (code "19") (name "LEDROW0") (class "Default")
      (node (ref "IC7") (pin "15") (pinfunction "QA_15") (pintype "tri_state"))
      (node (ref "LED1") (pin "A") (pinfunction "A_A") (pintype "passive"))
      (node (ref "LED105") (pin "A") (pinfunction "A_A") (pintype "passive"))
      (node (ref "LED113") (pin "A") (pinfunction "A_A") (pintype "passive"))
      (node (ref "LED17") (pin "A") (pinfunction "A_A") (pintype "passive"))
      (node (ref "LED25") (pin "A") (pinfunction "A_A") (pintype "passive"))
      (node (ref "LED33") (pin "A") (pinfunction "A_A") (pintype "passive"))
      (node (ref "LED41") (pin "A") (pinfunction "A_A") (pintype "passive"))
      (node (ref "LED49") (pin "A") (pinfunction "A_A") (pintype "passive"))
      (node (ref "LED57") (pin "A") (pinfunction "A_A") (pintype "passive"))
      (node (ref "LED65") (pin "A") (pinfunction "A_A") (pintype "passive"))
      (node (ref "LED73") (pin "A") (pinfunction "A_A") (pintype "passive"))
      (node (ref "LED81") (pin "A") (pinfunction "A_A") (pintype "passive"))
      (node (ref "LED89") (pin "A") (pinfunction "A_A") (pintype "passive"))
      (node (ref "LED9") (pin "A") (pinfunction "A_A") (pintype "passive"))
      (node (ref "LED97") (pin "A") (pinfunction "A_A") (pintype "passive"))
    )
    (net (code "20") (name "LEDROW1") (class "Default")
      (node (ref "IC7") (pin "1") (pinfunction "QB_1") (pintype "tri_state"))
      (node (ref "LED10") (pin "A") (pinfunction "A_A") (pintype "passive"))
      (node (ref "LED106") (pin "A") (pinfunction "A_A") (pintype "passive"))
      (node (ref "LED114") (pin "A") (pinfunction "A_A") (pintype "passive"))
      (node (ref "LED18") (pin "A") (pinfunction "A_A") (pintype "passive"))
      (node (ref "LED2") (pin "A") (pinfunction "A_A") (pintype "passive"))
      (node (ref "LED26") (pin "A") (pinfunction "A_A") (pintype "passive"))
      (node (ref "LED34") (pin "A") (pinfunction "A_A") (pintype "passive"))
      (node (ref "LED42") (pin "A") (pinfunction "A_A") (pintype "passive"))
      (node (ref "LED50") (pin "A") (pinfunction "A_A") (pintype "passive"))
      (node (ref "LED58") (pin "A") (pinfunction "A_A") (pintype "passive"))
      (node (ref "LED66") (pin "A") (pinfunction "A_A") (pintype "passive"))
      (node (ref "LED74") (pin "A") (pinfunction "A_A") (pintype "passive"))
      (node (ref "LED82") (pin "A") (pinfunction "A_A") (pintype "passive"))
      (node (ref "LED90") (pin "A") (pinfunction "A_A") (pintype "passive"))
      (node (ref "LED98") (pin "A") (pinfunction "A_A") (pintype "passive"))
    )
    (net (code "21") (name "LEDROW2") (class "Default")
      (node (ref "IC7") (pin "2") (pinfunction "QC_2") (pintype "tri_state"))
      (node (ref "LED107") (pin "A") (pinfunction "A_A") (pintype "passive"))
      (node (ref "LED11") (pin "A") (pinfunction "A_A") (pintype "passive"))
      (node (ref "LED115") (pin "A") (pinfunction "A_A") (pintype "passive"))
      (node (ref "LED19") (pin "A") (pinfunction "A_A") (pintype "passive"))
      (node (ref "LED27") (pin "A") (pinfunction "A_A") (pintype "passive"))
      (node (ref "LED3") (pin "A") (pinfunction "A_A") (pintype "passive"))
      (node (ref "LED35") (pin "A") (pinfunction "A_A") (pintype "passive"))
      (node (ref "LED43") (pin "A") (pinfunction "A_A") (pintype "passive"))
      (node (ref "LED51") (pin "A") (pinfunction "A_A") (pintype "passive"))
      (node (ref "LED59") (pin "A") (pinfunction "A_A") (pintype "passive"))
      (node (ref "LED67") (pin "A") (pinfunction "A_A") (pintype "passive"))
      (node (ref "LED75") (pin "A") (pinfunction "A_A") (pintype "passive"))
      (node (ref "LED83") (pin "A") (pinfunction "A_A") (pintype "passive"))
      (node (ref "LED91") (pin "A") (pinfunction "A_A") (pintype "passive"))
      (node (ref "LED99") (pin "A") (pinfunction "A_A") (pintype "passive"))
    )
    (net (code "22") (name "LEDROW3") (class "Default")
      (node (ref "IC7") (pin "3") (pinfunction "QD_3") (pintype "tri_state"))
      (node (ref "LED100") (pin "A") (pinfunction "A_A") (pintype "passive"))
      (node (ref "LED108") (pin "A") (pinfunction "A_A") (pintype "passive"))
      (node (ref "LED116") (pin "A") (pinfunction "A_A") (pintype "passive"))
      (node (ref "LED12") (pin "A") (pinfunction "A_A") (pintype "passive"))
      (node (ref "LED20") (pin "A") (pinfunction "A_A") (pintype "passive"))
      (node (ref "LED28") (pin "A") (pinfunction "A_A") (pintype "passive"))
      (node (ref "LED36") (pin "A") (pinfunction "A_A") (pintype "passive"))
      (node (ref "LED4") (pin "A") (pinfunction "A_A") (pintype "passive"))
      (node (ref "LED44") (pin "A") (pinfunction "A_A") (pintype "passive"))
      (node (ref "LED52") (pin "A") (pinfunction "A_A") (pintype "passive"))
      (node (ref "LED60") (pin "A") (pinfunction "A_A") (pintype "passive"))
      (node (ref "LED68") (pin "A") (pinfunction "A_A") (pintype "passive"))
      (node (ref "LED76") (pin "A") (pinfunction "A_A") (pintype "passive"))
      (node (ref "LED84") (pin "A") (pinfunction "A_A") (pintype "passive"))
      (node (ref "LED92") (pin "A") (pinfunction "A_A") (pintype "passive"))
    )
    (net (code "23") (name "LEDROW4") (class "Default")
      (node (ref "IC7") (pin "4") (pinfunction "QE_4") (pintype "tri_state"))
      (node (ref "LED101") (pin "A") (pinfunction "A_A") (pintype "passive"))
      (node (ref "LED109") (pin "A") (pinfunction "A_A") (pintype "passive"))
      (node (ref "LED117") (pin "A") (pinfunction "A_A") (pintype "passive"))
      (node (ref "LED13") (pin "A") (pinfunction "A_A") (pintype "passive"))
      (node (ref "LED21") (pin "A") (pinfunction "A_A") (pintype "passive"))
      (node (ref "LED29") (pin "A") (pinfunction "A_A") (pintype "passive"))
      (node (ref "LED37") (pin "A") (pinfunction "A_A") (pintype "passive"))
      (node (ref "LED45") (pin "A") (pinfunction "A_A") (pintype "passive"))
      (node (ref "LED5") (pin "A") (pinfunction "A_A") (pintype "passive"))
      (node (ref "LED53") (pin "A") (pinfunction "A_A") (pintype "passive"))
      (node (ref "LED61") (pin "A") (pinfunction "A_A") (pintype "passive"))
      (node (ref "LED69") (pin "A") (pinfunction "A_A") (pintype "passive"))
      (node (ref "LED77") (pin "A") (pinfunction "A_A") (pintype "passive"))
      (node (ref "LED85") (pin "A") (pinfunction "A_A") (pintype "passive"))
      (node (ref "LED93") (pin "A") (pinfunction "A_A") (pintype "passive"))
    )
    (net (code "24") (name "LEDROW5") (class "Default")
      (node (ref "IC7") (pin "5") (pinfunction "QF_5") (pintype "tri_state"))
      (node (ref "LED102") (pin "A") (pinfunction "A_A") (pintype "passive"))
      (node (ref "LED110") (pin "A") (pinfunction "A_A") (pintype "passive"))
      (node (ref "LED118") (pin "A") (pinfunction "A_A") (pintype "passive"))
      (node (ref "LED14") (pin "A") (pinfunction "A_A") (pintype "passive"))
      (node (ref "LED22") (pin "A") (pinfunction "A_A") (pintype "passive"))
      (node (ref "LED30") (pin "A") (pinfunction "A_A") (pintype "passive"))
      (node (ref "LED38") (pin "A") (pinfunction "A_A") (pintype "passive"))
      (node (ref "LED46") (pin "A") (pinfunction "A_A") (pintype "passive"))
      (node (ref "LED54") (pin "A") (pinfunction "A_A") (pintype "passive"))
      (node (ref "LED6") (pin "A") (pinfunction "A_A") (pintype "passive"))
      (node (ref "LED62") (pin "A") (pinfunction "A_A") (pintype "passive"))
      (node (ref "LED70") (pin "A") (pinfunction "A_A") (pintype "passive"))
      (node (ref "LED78") (pin "A") (pinfunction "A_A") (pintype "passive"))
      (node (ref "LED86") (pin "A") (pinfunction "A_A") (pintype "passive"))
      (node (ref "LED94") (pin "A") (pinfunction "A_A") (pintype "passive"))
    )
    (net (code "25") (name "LEDROW6") (class "Default")
      (node (ref "IC7") (pin "6") (pinfunction "QG_6") (pintype "tri_state"))
      (node (ref "LED103") (pin "A") (pinfunction "A_A") (pintype "passive"))
      (node (ref "LED111") (pin "A") (pinfunction "A_A") (pintype "passive"))
      (node (ref "LED119") (pin "A") (pinfunction "A_A") (pintype "passive"))
      (node (ref "LED15") (pin "A") (pinfunction "A_A") (pintype "passive"))
      (node (ref "LED23") (pin "A") (pinfunction "A_A") (pintype "passive"))
      (node (ref "LED31") (pin "A") (pinfunction "A_A") (pintype "passive"))
      (node (ref "LED39") (pin "A") (pinfunction "A_A") (pintype "passive"))
      (node (ref "LED47") (pin "A") (pinfunction "A_A") (pintype "passive"))
      (node (ref "LED55") (pin "A") (pinfunction "A_A") (pintype "passive"))
      (node (ref "LED63") (pin "A") (pinfunction "A_A") (pintype "passive"))
      (node (ref "LED7") (pin "A") (pinfunction "A_A") (pintype "passive"))
      (node (ref "LED71") (pin "A") (pinfunction "A_A") (pintype "passive"))
      (node (ref "LED79") (pin "A") (pinfunction "A_A") (pintype "passive"))
      (node (ref "LED87") (pin "A") (pinfunction "A_A") (pintype "passive"))
      (node (ref "LED95") (pin "A") (pinfunction "A_A") (pintype "passive"))
    )
    (net (code "26") (name "LEDROW7") (class "Default")
      (node (ref "IC7") (pin "7") (pinfunction "QH_7") (pintype "tri_state"))
      (node (ref "LED104") (pin "A") (pinfunction "A_A") (pintype "passive"))
      (node (ref "LED112") (pin "A") (pinfunction "A_A") (pintype "passive"))
      (node (ref "LED120") (pin "A") (pinfunction "A_A") (pintype "passive"))
      (node (ref "LED16") (pin "A") (pinfunction "A_A") (pintype "passive"))
      (node (ref "LED24") (pin "A") (pinfunction "A_A") (pintype "passive"))
      (node (ref "LED32") (pin "A") (pinfunction "A_A") (pintype "passive"))
      (node (ref "LED40") (pin "A") (pinfunction "A_A") (pintype "passive"))
      (node (ref "LED48") (pin "A") (pinfunction "A_A") (pintype "passive"))
      (node (ref "LED56") (pin "A") (pinfunction "A_A") (pintype "passive"))
      (node (ref "LED64") (pin "A") (pinfunction "A_A") (pintype "passive"))
      (node (ref "LED72") (pin "A") (pinfunction "A_A") (pintype "passive"))
      (node (ref "LED8") (pin "A") (pinfunction "A_A") (pintype "passive"))
      (node (ref "LED80") (pin "A") (pinfunction "A_A") (pintype "passive"))
      (node (ref "LED88") (pin "A") (pinfunction "A_A") (pintype "passive"))
      (node (ref "LED96") (pin "A") (pinfunction "A_A") (pintype "passive"))
    )
    (net (code "27") (name "MOSFET_STATUS") (class "Default")
      (node (ref "Q1") (pin "1") (pinfunction "B_1") (pintype "passive"))
      (node (ref "R16") (pin "2") (pinfunction "2_2") (pintype "passive"))
    )
    (net (code "28") (name "MOSI") (class "Default")
      (node (ref "IC6") (pin "15") (pinfunction "PB3(MOSI/OC2)_15") (pintype "bidirectional"))
      (node (ref "Q1") (pin "2") (pinfunction "E_2") (pintype "passive"))
      (node (ref "TP2") (pin "TP") (pinfunction "TP_TP") (pintype "input"))
    )
    (net (code "29") (name "Net-(F1-Pad2)") (class "Default")
      (node (ref "F1") (pin "2") (pinfunction "2_2") (pintype "passive"))
      (node (ref "X1") (pin "VBUS") (pinfunction "VBUS_VBUS") (pintype "bidirectional"))
    )
    (net (code "30") (name "Net-(IC1-DIN)") (class "Default")
      (node (ref "IC1") (pin "6") (pinfunction "DIN_6") (pintype "input"))
      (node (ref "R2") (pin "2") (pinfunction "2_2") (pintype "passive"))
    )
    (net (code "31") (name "Net-(IC1-DO)") (class "Default")
      (node (ref "IC1") (pin "5") (pinfunction "DO_5") (pintype "output"))
      (node (ref "R1") (pin "2") (pinfunction "2_2") (pintype "passive"))
    )
    (net (code "32") (name "Net-(IC1-SET)") (class "Default")
      (node (ref "IC1") (pin "7") (pinfunction "SET_7") (pintype "input"))
      (node (ref "R3") (pin "2") (pinfunction "2_2") (pintype "passive"))
    )
    (net (code "33") (name "Net-(IC2-DIN)") (class "Default")
      (node (ref "IC2") (pin "6") (pinfunction "DIN_6") (pintype "input"))
      (node (ref "R5") (pin "2") (pinfunction "2_2") (pintype "passive"))
    )
    (net (code "34") (name "Net-(IC2-DO)") (class "Default")
      (node (ref "IC2") (pin "5") (pinfunction "DO_5") (pintype "output"))
      (node (ref "R4") (pin "2") (pinfunction "2_2") (pintype "passive"))
    )
    (net (code "35") (name "Net-(IC2-SET)") (class "Default")
      (node (ref "IC2") (pin "7") (pinfunction "SET_7") (pintype "input"))
      (node (ref "R6") (pin "2") (pinfunction "2_2") (pintype "passive"))
    )
    (net (code "36") (name "Net-(IC3-DIN)") (class "Default")
      (node (ref "IC3") (pin "6") (pinfunction "DIN_6") (pintype "input"))
      (node (ref "R8") (pin "2") (pinfunction "2_2") (pintype "passive"))
    )
    (net (code "37") (name "Net-(IC3-DO)") (class "Default")
      (node (ref "IC3") (pin "5") (pinfunction "DO_5") (pintype "output"))
      (node (ref "R7") (pin "2") (pinfunction "2_2") (pintype "passive"))
    )
    (net (code "38") (name "Net-(IC3-SET)") (class "Default")
      (node (ref "IC3") (pin "7") (pinfunction "SET_7") (pintype "input"))
      (node (ref "R9") (pin "2") (pinfunction "2_2") (pintype "passive"))
    )
    (net (code "39") (name "Net-(IC4-DIN)") (class "Default")
      (node (ref "IC4") (pin "6") (pinfunction "DIN_6") (pintype "input"))
      (node (ref "R11") (pin "2") (pinfunction "2_2") (pintype "passive"))
    )
    (net (code "40") (name "Net-(IC4-DO)") (class "Default")
      (node (ref "IC4") (pin "5") (pinfunction "DO_5") (pintype "output"))
      (node (ref "R10") (pin "2") (pinfunction "2_2") (pintype "passive"))
    )
    (net (code "41") (name "Net-(IC4-SET)") (class "Default")
      (node (ref "IC4") (pin "7") (pinfunction "SET_7") (pintype "input"))
      (node (ref "R12") (pin "2") (pinfunction "2_2") (pintype "passive"))
    )
    (net (code "42") (name "Net-(IC5-DIN)") (class "Default")
      (node (ref "IC5") (pin "6") (pinfunction "DIN_6") (pintype "input"))
      (node (ref "R13") (pin "2") (pinfunction "2_2") (pintype "passive"))
    )
    (net (code "43") (name "Net-(IC5-SET)") (class "Default")
      (node (ref "IC5") (pin "7") (pinfunction "SET_7") (pintype "input"))
      (node (ref "R14") (pin "2") (pinfunction "2_2") (pintype "passive"))
    )
    (net (code "44") (name "Net-(IC6-PB6(XTAL1{slash}TOSC1))") (class "Default")
      (node (ref "C11") (pin "2") (pinfunction "2_2") (pintype "passive"))
      (node (ref "IC6") (pin "7") (pinfunction "PB6(XTAL1/TOSC1)_7") (pintype "bidirectional"))
      (node (ref "X2") (pin "P$2") (pinfunction "P$2_P$2") (pintype "bidirectional"))
    )
    (net (code "45") (name "Net-(IC6-PB7(XTAL2{slash}TOSC2))") (class "Default")
      (node (ref "C12") (pin "2") (pinfunction "2_2") (pintype "passive"))
      (node (ref "IC6") (pin "8") (pinfunction "PB7(XTAL2/TOSC2)_8") (pintype "bidirectional"))
      (node (ref "X2") (pin "P$1") (pinfunction "P$1_P$1") (pintype "bidirectional"))
    )
    (net (code "46") (name "Net-(IC6-PD2(INT0))") (class "Default")
      (node (ref "IC6") (pin "32") (pinfunction "PD2(INT0)_32") (pintype "bidirectional"))
      (node (ref "S2") (pin "1") (pinfunction "2_1") (pintype "passive"))
    )
    (net (code "47") (name "Net-(R1-Pad1)") (class "Default")
      (node (ref "R1") (pin "1") (pinfunction "1_1") (pintype "passive"))
      (node (ref "R5") (pin "1") (pinfunction "1_1") (pintype "passive"))
    )
    (net (code "48") (name "Net-(R4-Pad1)") (class "Default")
      (node (ref "R4") (pin "1") (pinfunction "1_1") (pintype "passive"))
      (node (ref "R8") (pin "1") (pinfunction "1_1") (pintype "passive"))
    )
    (net (code "49") (name "Net-(R10-Pad1)") (class "Default")
      (node (ref "R10") (pin "1") (pinfunction "1_1") (pintype "passive"))
      (node (ref "R13") (pin "1") (pinfunction "1_1") (pintype "passive"))
    )
    (net (code "50") (name "Net-(R11-Pad1)") (class "Default")
      (node (ref "R11") (pin "1") (pinfunction "1_1") (pintype "passive"))
      (node (ref "R7") (pin "1") (pinfunction "1_1") (pintype "passive"))
    )
    (net (code "51") (name "Net-(S1-2)") (class "Default")
      (node (ref "R15") (pin "1") (pinfunction "1_1") (pintype "passive"))
      (node (ref "S1") (pin "1") (pinfunction "2_1") (pintype "passive"))
    )
    (net (code "52") (name "Net-(S2-1)") (class "Default")
      (node (ref "R17") (pin "2") (pinfunction "2_2") (pintype "passive"))
      (node (ref "S2") (pin "2") (pinfunction "1_2") (pintype "passive"))
    )
    (net (code "53") (name "RCK") (class "Default")
      (node (ref "IC6") (pin "2") (pinfunction "PD4(XCK/T0)_2") (pintype "bidirectional"))
      (node (ref "IC7") (pin "12") (pinfunction "RCK_12") (pintype "input"))
    )
    (net (code "54") (name "RES") (class "Default")
      (node (ref "IC6") (pin "29") (pinfunction "PC6(/RESET)_29") (pintype "bidirectional"))
      (node (ref "R16") (pin "1") (pinfunction "1_1") (pintype "passive"))
      (node (ref "S1") (pin "2") (pinfunction "1_2") (pintype "passive"))
    )
    (net (code "55") (name "SCK") (class "Default")
      (node (ref "IC6") (pin "10") (pinfunction "PD6(AIN0)_10") (pintype "bidirectional"))
      (node (ref "IC7") (pin "11") (pinfunction "SCK_11") (pintype "input"))
    )
    (net (code "56") (name "SCL") (class "Default")
      (node (ref "IC6") (pin "9") (pinfunction "PD5(T1)_9") (pintype "bidirectional"))
      (node (ref "IC7") (pin "10") (pinfunction "SCL_10") (pintype "input"))
    )
    (net (code "57") (name "SER") (class "Default")
      (node (ref "IC6") (pin "11") (pinfunction "PD7(AIN1)_11") (pintype "bidirectional"))
      (node (ref "IC7") (pin "14") (pinfunction "SER_14") (pintype "input"))
    )
    (net (code "58") (name "SHIFT_G") (class "Default")
      (node (ref "IC6") (pin "1") (pinfunction "PD3(INT1)_1") (pintype "bidirectional"))
      (node (ref "IC7") (pin "13") (pinfunction "G_13") (pintype "input"))
    )
    (net (code "59") (name "VCC") (class "Default")
      (node (ref "C10") (pin "1") (pinfunction "1_1") (pintype "passive"))
      (node (ref "C2") (pin "1") (pinfunction "1_1") (pintype "passive"))
      (node (ref "C3") (pin "1") (pinfunction "1_1") (pintype "passive"))
      (node (ref "C4") (pin "1") (pinfunction "1_1") (pintype "passive"))
      (node (ref "C7") (pin "1") (pinfunction "1_1") (pintype "passive"))
      (node (ref "C8") (pin "1") (pinfunction "1_1") (pintype "passive"))
      (node (ref "C9") (pin "1") (pinfunction "1_1") (pintype "passive"))
      (node (ref "D1") (pin "C") (pinfunction "C_C") (pintype "passive"))
      (node (ref "F1") (pin "1") (pinfunction "1_1") (pintype "passive"))
      (node (ref "IC1") (pin "8") (pinfunction "VDD_8") (pintype "power_in"))
      (node (ref "IC2") (pin "8") (pinfunction "VDD_8") (pintype "power_in"))
      (node (ref "IC3") (pin "8") (pinfunction "VDD_8") (pintype "power_in"))
      (node (ref "IC4") (pin "8") (pinfunction "VDD_8") (pintype "power_in"))
      (node (ref "IC5") (pin "8") (pinfunction "VDD_8") (pintype "power_in"))
      (node (ref "R12") (pin "1") (pinfunction "1_1") (pintype "passive"))
      (node (ref "R14") (pin "1") (pinfunction "1_1") (pintype "passive"))
      (node (ref "R3") (pin "1") (pinfunction "1_1") (pintype "passive"))
      (node (ref "R6") (pin "1") (pinfunction "1_1") (pintype "passive"))
      (node (ref "R9") (pin "1") (pinfunction "1_1") (pintype "passive"))
      (node (ref "U1") (pin "3") (pinfunction "IN_3") (pintype "input"))
    )
    (net (code "60") (name "unconnected-(IC5-DO-Pad5)") (class "Default")
      (node (ref "IC5") (pin "5") (pinfunction "DO_5") (pintype "output"))
    )
    (net (code "61") (name "unconnected-(IC6-ADC6-Pad19)") (class "Default")
      (node (ref "IC6") (pin "19") (pinfunction "ADC6_19") (pintype "bidirectional"))
    )
    (net (code "62") (name "unconnected-(IC6-ADC7-Pad22)") (class "Default")
      (node (ref "IC6") (pin "22") (pinfunction "ADC7_22") (pintype "bidirectional"))
    )
    (net (code "63") (name "unconnected-(IC6-AREF-Pad20)") (class "Default")
      (node (ref "IC6") (pin "20") (pinfunction "AREF_20") (pintype "passive"))
    )
    (net (code "64") (name "unconnected-(IC6-PB0(ICP)-Pad12)") (class "Default")
      (node (ref "IC6") (pin "12") (pinfunction "PB0(ICP)_12") (pintype "bidirectional"))
    )
    (net (code "65") (name "unconnected-(IC6-PB1(OC1A)-Pad13)") (class "Default")
      (node (ref "IC6") (pin "13") (pinfunction "PB1(OC1A)_13") (pintype "bidirectional"))
    )
    (net (code "66") (name "unconnected-(IC6-PB2(SS{slash}OC1B)-Pad14)") (class "Default")
      (node (ref "IC6") (pin "14") (pinfunction "PB2(SS/OC1B)_14") (pintype "bidirectional"))
    )
    (net (code "67") (name "unconnected-(IC6-PB4(MISO)-Pad16)") (class "Default")
      (node (ref "IC6") (pin "16") (pinfunction "PB4(MISO)_16") (pintype "bidirectional"))
    )
    (net (code "68") (name "unconnected-(IC6-PB5(SCK)-Pad17)") (class "Default")
      (node (ref "IC6") (pin "17") (pinfunction "PB5(SCK)_17") (pintype "bidirectional"))
    )
    (net (code "69") (name "unconnected-(IC6-PC0(ADC0)-Pad23)") (class "Default")
      (node (ref "IC6") (pin "23") (pinfunction "PC0(ADC0)_23") (pintype "bidirectional"))
    )
    (net (code "70") (name "unconnected-(IC6-PC1(ADC1)-Pad24)") (class "Default")
      (node (ref "IC6") (pin "24") (pinfunction "PC1(ADC1)_24") (pintype "bidirectional"))
    )
    (net (code "71") (name "unconnected-(IC6-PC2(ADC2)-Pad25)") (class "Default")
      (node (ref "IC6") (pin "25") (pinfunction "PC2(ADC2)_25") (pintype "bidirectional"))
    )
    (net (code "72") (name "unconnected-(IC6-PC3(ADC3)-Pad26)") (class "Default")
      (node (ref "IC6") (pin "26") (pinfunction "PC3(ADC3)_26") (pintype "bidirectional"))
    )
    (net (code "73") (name "unconnected-(IC6-PC4(ADC4{slash}SDA)-Pad27)") (class "Default")
      (node (ref "IC6") (pin "27") (pinfunction "PC4(ADC4/SDA)_27") (pintype "bidirectional"))
    )
    (net (code "74") (name "unconnected-(IC6-PC5(ADC5{slash}SCL)-Pad28)") (class "Default")
      (node (ref "IC6") (pin "28") (pinfunction "PC5(ADC5/SCL)_28") (pintype "bidirectional"))
    )
    (net (code "75") (name "unconnected-(IC6-PD0(RXD)-Pad30)") (class "Default")
      (node (ref "IC6") (pin "30") (pinfunction "PD0(RXD)_30") (pintype "bidirectional"))
    )
    (net (code "76") (name "unconnected-(IC6-PD1(TXD)-Pad31)") (class "Default")
      (node (ref "IC6") (pin "31") (pinfunction "PD1(TXD)_31") (pintype "bidirectional"))
    )
    (net (code "77") (name "unconnected-(IC7A-QH*-Pad9)") (class "Default")
      (node (ref "IC7") (pin "9") (pinfunction "QH*_9") (pintype "tri_state"))
    )
    (net (code "78") (name "unconnected-(X1-PadD+)") (class "Default")
      (node (ref "X1") (pin "D+") (pinfunction "D+_D+") (pintype "bidirectional"))
    )
    (net (code "79") (name "unconnected-(X1-PadD-)") (class "Default")
      (node (ref "X1") (pin "D-") (pinfunction "D-_D-") (pintype "bidirectional"))
    )
  )
)
